# FFB_Arduino_Yoke_1_3_Micro.net
KiCad netlist of a schematic drawn in EasyEDA
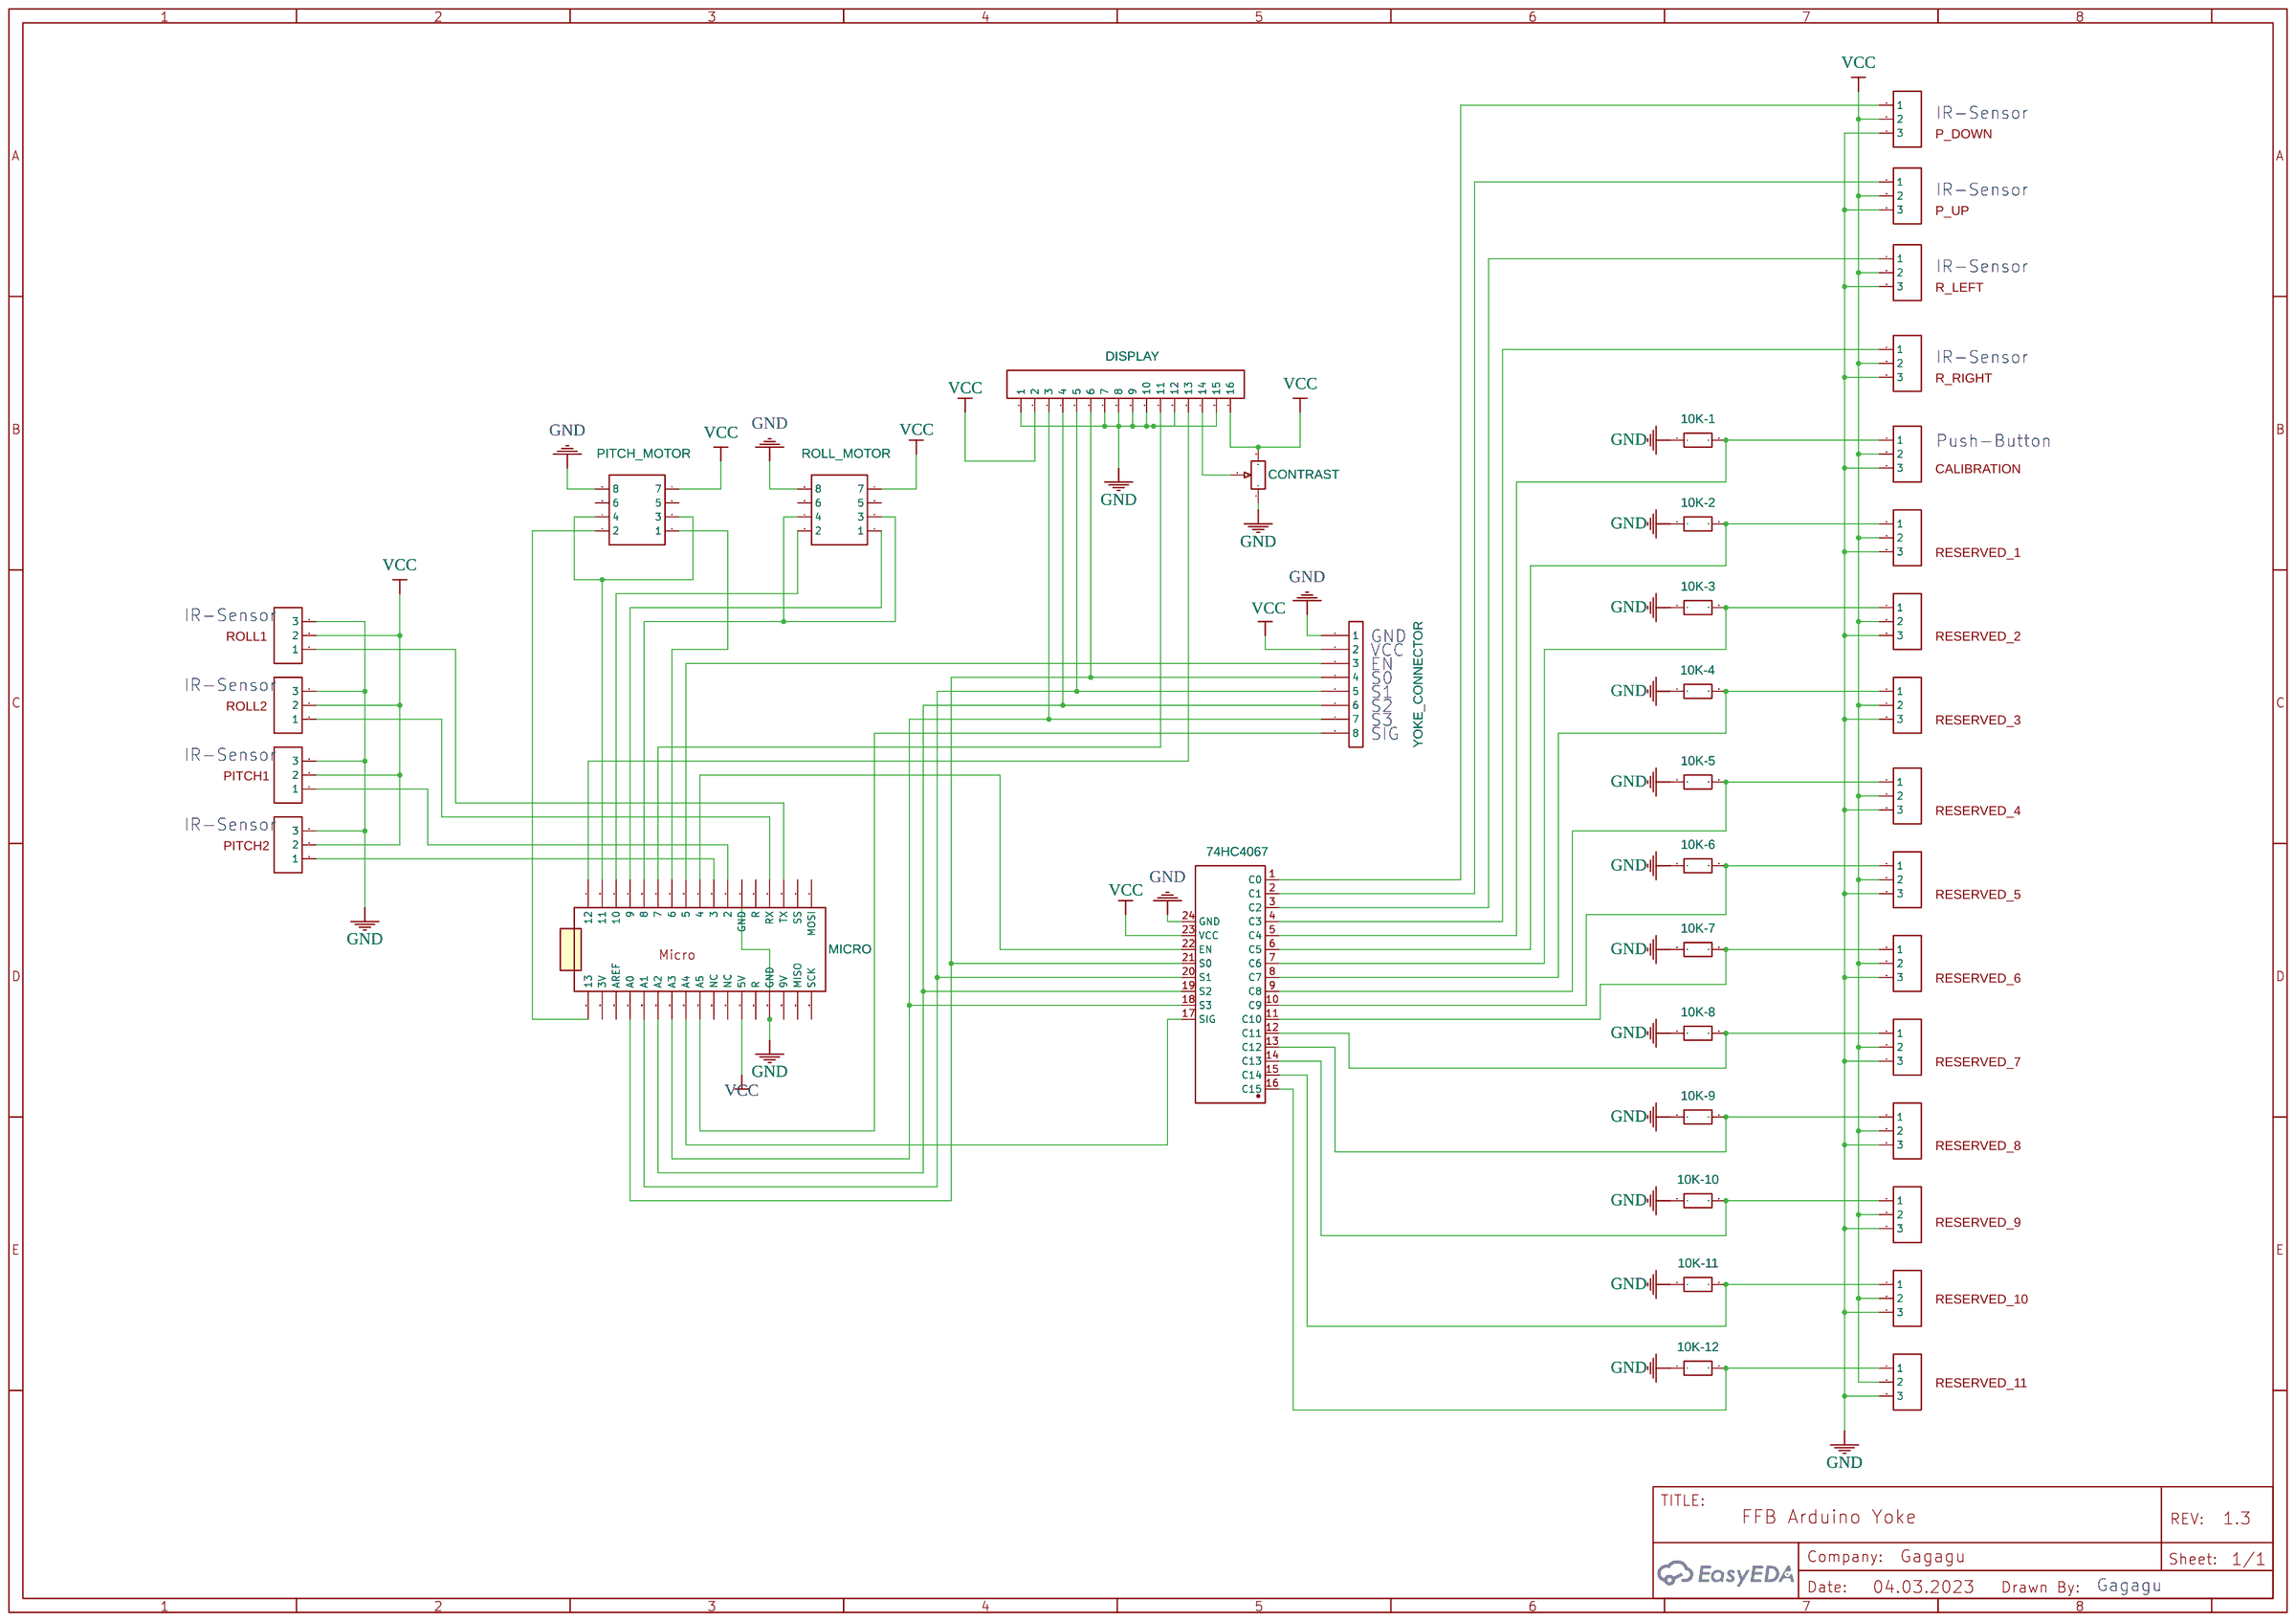
[diagram p0: schematic sheet]

(export (version "E")
  (design (tool "Eeschema 10.0.6"))
  (components
    (comp (ref "10K-1") (value "10k") (libsource (lib "") (part "R_AXIAL-0.3_EU")))
    (comp (ref "10K-2") (value "10k") (libsource (lib "") (part "R_AXIAL-0.3_EU")))
    (comp (ref "10K-3") (value "10k") (libsource (lib "") (part "R_AXIAL-0.3_EU")))
    (comp (ref "10K-4") (value "10k") (libsource (lib "") (part "R_AXIAL-0.3_EU")))
    (comp (ref "10K-5") (value "10k") (libsource (lib "") (part "R_AXIAL-0.3_EU")))
    (comp (ref "10K-6") (value "10k") (libsource (lib "") (part "R_AXIAL-0.3_EU")))
    (comp (ref "10K-7") (value "10k") (libsource (lib "") (part "R_AXIAL-0.3_EU")))
    (comp (ref "10K-8") (value "10k") (libsource (lib "") (part "R_AXIAL-0.3_EU")))
    (comp (ref "10K-9") (value "10k") (libsource (lib "") (part "R_AXIAL-0.3_EU")))
    (comp (ref "10K-10") (value "10k") (libsource (lib "") (part "R_AXIAL-0.3_EU")))
    (comp (ref "10K-11") (value "10k") (libsource (lib "") (part "R_AXIAL-0.3_EU")))
    (comp (ref "10K-12") (value "10k") (libsource (lib "") (part "R_AXIAL-0.3_EU")))
    (comp (ref "74HC4067")
      (value "MUX CD74HC4067")
      (fields (field (name "BOM_Supplier Part") "420243"))
      (libsource (lib "") (part "16-Kanal Analog/Digital Multiplexer MUX CD74HC4067"))
    )
    (comp (ref "CALIBR.")
      (value "Multiturn POT 10K")
      (fields (field (name "BOM_Supplier Part") "C146690"))
      (libsource (lib "") (part "HDR-F-2.54_1x3_9"))
    )
    (comp (ref "CONTRAST") (value "R_3386P_EU") (libsource (lib "") (part "R_3386P_EU")))
    (comp (ref "DISPLAY") (value "HDR-M-2.54_1x16") (libsource (lib "") (part "HDR-M-2.54_1x16")))
    (comp (ref "MICRO") (value "ARDUINOMICRO") (libsource (lib "") (part "ARDUINOMICRO")))
    (comp (ref "PITCH1")
      (value "Multiturn POT 10K")
      (fields (field (name "BOM_Supplier Part") "C146690"))
      (libsource (lib "") (part "HDR-F-2.54_1x3"))
    )
    (comp (ref "PITCH2")
      (value "Multiturn POT 10K")
      (fields (field (name "BOM_Supplier Part") "C146690"))
      (libsource (lib "") (part "HDR-F-2.54_1x3_17"))
    )
    (comp (ref "PITCH_MOTOR")
      (value "HDR-F-2.54_2x4")
      (fields (field (name "BOM_Supplier Part") "C239344"))
      (libsource (lib "") (part "HDR-F-2.54_2x4"))
    )
    (comp (ref "P_DOWN")
      (value "Multiturn POT 10K")
      (fields (field (name "BOM_Supplier Part") "C146690"))
      (libsource (lib "") (part "HDR-F-2.54_1x3_1"))
    )
    (comp (ref "P_UP")
      (value "Multiturn POT 10K")
      (fields (field (name "BOM_Supplier Part") "C146690"))
      (libsource (lib "") (part "HDR-F-2.54_1x3_18"))
    )
    (comp (ref "RES_1")
      (value "Multiturn POT 10K")
      (fields (field (name "BOM_Supplier Part") "C146690"))
      (libsource (lib "") (part "HDR-F-2.54_1x3_6"))
    )
    (comp (ref "RES_2")
      (value "Multiturn POT 10K")
      (fields (field (name "BOM_Supplier Part") "C146690"))
      (libsource (lib "") (part "HDR-F-2.54_1x3_11"))
    )
    (comp (ref "RES_3")
      (value "Multiturn POT 10K")
      (fields (field (name "BOM_Supplier Part") "C146690"))
      (libsource (lib "") (part "HDR-F-2.54_1x3_7"))
    )
    (comp (ref "RES_4")
      (value "Multiturn POT 10K")
      (fields (field (name "BOM_Supplier Part") "C146690"))
      (libsource (lib "") (part "HDR-F-2.54_1x3_19"))
    )
    (comp (ref "RES_5")
      (value "Multiturn POT 10K")
      (fields (field (name "BOM_Supplier Part") "C146690"))
      (libsource (lib "") (part "HDR-F-2.54_1x3_8"))
    )
    (comp (ref "RES_6")
      (value "Multiturn POT 10K")
      (fields (field (name "BOM_Supplier Part") "C146690"))
      (libsource (lib "") (part "HDR-F-2.54_1x3_16"))
    )
    (comp (ref "RES_7")
      (value "Multiturn POT 10K")
      (fields (field (name "BOM_Supplier Part") "C146690"))
      (libsource (lib "") (part "HDR-F-2.54_1x3_3"))
    )
    (comp (ref "RES_8")
      (value "Multiturn POT 10K")
      (fields (field (name "BOM_Supplier Part") "C146690"))
      (libsource (lib "") (part "HDR-F-2.54_1x3_10"))
    )
    (comp (ref "RES_9")
      (value "Multiturn POT 10K")
      (fields (field (name "BOM_Supplier Part") "C146690"))
      (libsource (lib "") (part "HDR-F-2.54_1x3_13"))
    )
    (comp (ref "RES_10")
      (value "Multiturn POT 10K")
      (fields (field (name "BOM_Supplier Part") "C146690"))
      (libsource (lib "") (part "HDR-F-2.54_1x3_14"))
    )
    (comp (ref "RES_11")
      (value "Multiturn POT 10K")
      (fields (field (name "BOM_Supplier Part") "C146690"))
      (libsource (lib "") (part "HDR-F-2.54_1x3_2"))
    )
    (comp (ref "ROLL1")
      (value "Multiturn POT 10K")
      (fields (field (name "BOM_Supplier Part") "C146690"))
      (libsource (lib "") (part "HDR-F-2.54_1x3_4"))
    )
    (comp (ref "ROLL2")
      (value "Multiturn POT 10K")
      (fields (field (name "BOM_Supplier Part") "C146690"))
      (libsource (lib "") (part "HDR-F-2.54_1x3_12"))
    )
    (comp (ref "ROLL_MOTOR")
      (value "HDR-F-2.54_2x4")
      (fields (field (name "BOM_Supplier Part") "C239344"))
      (libsource (lib "") (part "HDR-F-2.54_2x4_1"))
    )
    (comp (ref "R_LEFT")
      (value "Multiturn POT 10K")
      (fields (field (name "BOM_Supplier Part") "C146690"))
      (libsource (lib "") (part "HDR-F-2.54_1x3_15"))
    )
    (comp (ref "R_RIGHT")
      (value "Multiturn POT 10K")
      (fields (field (name "BOM_Supplier Part") "C146690"))
      (libsource (lib "") (part "HDR-F-2.54_1x3_5"))
    )
    (comp (ref "YOKE_CONNECTOR")
      (value "Yoke Connector")
      (fields (field (name "BOM_Manufacturer Part") "Conector_dupont"))
      (libsource (lib "") (part "DUPONT_1X8"))
    )
  )
  (nets
    (net (code "1") (name "GND") (class "Default")
      (node (ref "10K-1") (pin "1") (pinfunction "1_1") (pintype "unspecified"))
      (node (ref "10K-10") (pin "1") (pinfunction "1_1") (pintype "unspecified"))
      (node (ref "10K-11") (pin "1") (pinfunction "1_1") (pintype "unspecified"))
      (node (ref "10K-12") (pin "1") (pinfunction "1_1") (pintype "unspecified"))
      (node (ref "10K-2") (pin "1") (pinfunction "1_1") (pintype "unspecified"))
      (node (ref "10K-3") (pin "1") (pinfunction "1_1") (pintype "unspecified"))
      (node (ref "10K-4") (pin "1") (pinfunction "1_1") (pintype "unspecified"))
      (node (ref "10K-5") (pin "1") (pinfunction "1_1") (pintype "unspecified"))
      (node (ref "10K-6") (pin "1") (pinfunction "1_1") (pintype "unspecified"))
      (node (ref "10K-7") (pin "1") (pinfunction "1_1") (pintype "unspecified"))
      (node (ref "10K-8") (pin "1") (pinfunction "1_1") (pintype "unspecified"))
      (node (ref "10K-9") (pin "1") (pinfunction "1_1") (pintype "unspecified"))
      (node (ref "74HC4067") (pin "24") (pinfunction "GND_24") (pintype "unspecified"))
      (node (ref "CALIBR.") (pin "3") (pinfunction "3_3") (pintype "unspecified"))
      (node (ref "CONTRAST") (pin "1") (pinfunction "1_1") (pintype "input"))
      (node (ref "DISPLAY") (pin "1") (pinfunction "1_1") (pintype "unspecified"))
      (node (ref "DISPLAY") (pin "10") (pinfunction "10_10") (pintype "unspecified"))
      (node (ref "DISPLAY") (pin "12") (pinfunction "12_12") (pintype "unspecified"))
      (node (ref "DISPLAY") (pin "15") (pinfunction "15_15") (pintype "unspecified"))
      (node (ref "DISPLAY") (pin "7") (pinfunction "7_7") (pintype "unspecified"))
      (node (ref "DISPLAY") (pin "8") (pinfunction "8_8") (pintype "unspecified"))
      (node (ref "DISPLAY") (pin "9") (pinfunction "9_9") (pintype "unspecified"))
      (node (ref "MICRO") (pin "P$12") (pinfunction "GND_P$12") (pintype "unspecified"))
      (node (ref "MICRO") (pin "P$21") (pinfunction "GND_P$21") (pintype "unspecified"))
      (node (ref "PITCH1") (pin "3") (pinfunction "3_3") (pintype "unspecified"))
      (node (ref "PITCH2") (pin "3") (pinfunction "3_3") (pintype "unspecified"))
      (node (ref "PITCH_MOTOR") (pin "8") (pinfunction "8_8") (pintype "unspecified"))
      (node (ref "P_DOWN") (pin "3") (pinfunction "3_3") (pintype "unspecified"))
      (node (ref "P_UP") (pin "3") (pinfunction "3_3") (pintype "unspecified"))
      (node (ref "RES_1") (pin "3") (pinfunction "3_3") (pintype "unspecified"))
      (node (ref "RES_10") (pin "3") (pinfunction "3_3") (pintype "unspecified"))
      (node (ref "RES_11") (pin "3") (pinfunction "3_3") (pintype "unspecified"))
      (node (ref "RES_2") (pin "3") (pinfunction "3_3") (pintype "unspecified"))
      (node (ref "RES_3") (pin "3") (pinfunction "3_3") (pintype "unspecified"))
      (node (ref "RES_4") (pin "3") (pinfunction "3_3") (pintype "unspecified"))
      (node (ref "RES_5") (pin "3") (pinfunction "3_3") (pintype "unspecified"))
      (node (ref "RES_6") (pin "3") (pinfunction "3_3") (pintype "unspecified"))
      (node (ref "RES_7") (pin "3") (pinfunction "3_3") (pintype "unspecified"))
      (node (ref "RES_8") (pin "3") (pinfunction "3_3") (pintype "unspecified"))
      (node (ref "RES_9") (pin "3") (pinfunction "3_3") (pintype "unspecified"))
      (node (ref "ROLL1") (pin "3") (pinfunction "3_3") (pintype "unspecified"))
      (node (ref "ROLL2") (pin "3") (pinfunction "3_3") (pintype "unspecified"))
      (node (ref "ROLL_MOTOR") (pin "8") (pinfunction "8_8") (pintype "unspecified"))
      (node (ref "R_LEFT") (pin "3") (pinfunction "3_3") (pintype "unspecified"))
      (node (ref "R_RIGHT") (pin "3") (pinfunction "3_3") (pintype "unspecified"))
      (node (ref "YOKE_CONNECTOR") (pin "1") (pinfunction "1_1") (pintype "unspecified"))
    )
    (net (code "2") (name "Net-(74HC4067-C0)") (class "Default")
      (node (ref "74HC4067") (pin "1") (pinfunction "C0_1") (pintype "unspecified"))
      (node (ref "P_DOWN") (pin "1") (pinfunction "1_1") (pintype "unspecified"))
    )
    (net (code "3") (name "Net-(74HC4067-C1)") (class "Default")
      (node (ref "74HC4067") (pin "2") (pinfunction "C1_2") (pintype "unspecified"))
      (node (ref "P_UP") (pin "1") (pinfunction "1_1") (pintype "unspecified"))
    )
    (net (code "4") (name "Net-(74HC4067-C2)") (class "Default")
      (node (ref "74HC4067") (pin "3") (pinfunction "C2_3") (pintype "unspecified"))
      (node (ref "R_LEFT") (pin "1") (pinfunction "1_1") (pintype "unspecified"))
    )
    (net (code "5") (name "Net-(74HC4067-C3)") (class "Default")
      (node (ref "74HC4067") (pin "4") (pinfunction "C3_4") (pintype "unspecified"))
      (node (ref "R_RIGHT") (pin "1") (pinfunction "1_1") (pintype "unspecified"))
    )
    (net (code "6") (name "Net-(74HC4067-C4)") (class "Default")
      (node (ref "10K-1") (pin "2") (pinfunction "2_2") (pintype "unspecified"))
      (node (ref "74HC4067") (pin "5") (pinfunction "C4_5") (pintype "unspecified"))
      (node (ref "CALIBR.") (pin "1") (pinfunction "1_1") (pintype "unspecified"))
    )
    (net (code "7") (name "Net-(74HC4067-C5)") (class "Default")
      (node (ref "10K-2") (pin "2") (pinfunction "2_2") (pintype "unspecified"))
      (node (ref "74HC4067") (pin "6") (pinfunction "C5_6") (pintype "unspecified"))
      (node (ref "RES_1") (pin "1") (pinfunction "1_1") (pintype "unspecified"))
    )
    (net (code "8") (name "Net-(74HC4067-C6)") (class "Default")
      (node (ref "10K-3") (pin "2") (pinfunction "2_2") (pintype "unspecified"))
      (node (ref "74HC4067") (pin "7") (pinfunction "C6_7") (pintype "unspecified"))
      (node (ref "RES_2") (pin "1") (pinfunction "1_1") (pintype "unspecified"))
    )
    (net (code "9") (name "Net-(74HC4067-C7)") (class "Default")
      (node (ref "10K-4") (pin "2") (pinfunction "2_2") (pintype "unspecified"))
      (node (ref "74HC4067") (pin "8") (pinfunction "C7_8") (pintype "unspecified"))
      (node (ref "RES_3") (pin "1") (pinfunction "1_1") (pintype "unspecified"))
    )
    (net (code "10") (name "Net-(74HC4067-C8)") (class "Default")
      (node (ref "10K-5") (pin "2") (pinfunction "2_2") (pintype "unspecified"))
      (node (ref "74HC4067") (pin "9") (pinfunction "C8_9") (pintype "unspecified"))
      (node (ref "RES_4") (pin "1") (pinfunction "1_1") (pintype "unspecified"))
    )
    (net (code "11") (name "Net-(74HC4067-C9)") (class "Default")
      (node (ref "10K-6") (pin "2") (pinfunction "2_2") (pintype "unspecified"))
      (node (ref "74HC4067") (pin "10") (pinfunction "C9_10") (pintype "unspecified"))
      (node (ref "RES_5") (pin "1") (pinfunction "1_1") (pintype "unspecified"))
    )
    (net (code "12") (name "Net-(74HC4067-C10)") (class "Default")
      (node (ref "10K-7") (pin "2") (pinfunction "2_2") (pintype "unspecified"))
      (node (ref "74HC4067") (pin "11") (pinfunction "C10_11") (pintype "unspecified"))
      (node (ref "RES_6") (pin "1") (pinfunction "1_1") (pintype "unspecified"))
    )
    (net (code "13") (name "Net-(74HC4067-C11)") (class "Default")
      (node (ref "10K-8") (pin "2") (pinfunction "2_2") (pintype "unspecified"))
      (node (ref "74HC4067") (pin "12") (pinfunction "C11_12") (pintype "unspecified"))
      (node (ref "RES_7") (pin "1") (pinfunction "1_1") (pintype "unspecified"))
    )
    (net (code "14") (name "Net-(74HC4067-C12)") (class "Default")
      (node (ref "10K-9") (pin "2") (pinfunction "2_2") (pintype "unspecified"))
      (node (ref "74HC4067") (pin "13") (pinfunction "C12_13") (pintype "unspecified"))
      (node (ref "RES_8") (pin "1") (pinfunction "1_1") (pintype "unspecified"))
    )
    (net (code "15") (name "Net-(74HC4067-C13)") (class "Default")
      (node (ref "10K-10") (pin "2") (pinfunction "2_2") (pintype "unspecified"))
      (node (ref "74HC4067") (pin "14") (pinfunction "C13_14") (pintype "unspecified"))
      (node (ref "RES_9") (pin "1") (pinfunction "1_1") (pintype "unspecified"))
    )
    (net (code "16") (name "Net-(74HC4067-C14)") (class "Default")
      (node (ref "10K-11") (pin "2") (pinfunction "2_2") (pintype "unspecified"))
      (node (ref "74HC4067") (pin "15") (pinfunction "C14_15") (pintype "unspecified"))
      (node (ref "RES_10") (pin "1") (pinfunction "1_1") (pintype "unspecified"))
    )
    (net (code "17") (name "Net-(74HC4067-C15)") (class "Default")
      (node (ref "10K-12") (pin "2") (pinfunction "2_2") (pintype "unspecified"))
      (node (ref "74HC4067") (pin "16") (pinfunction "C15_16") (pintype "unspecified"))
      (node (ref "RES_11") (pin "1") (pinfunction "1_1") (pintype "unspecified"))
    )
    (net (code "18") (name "Net-(74HC4067-EN)") (class "Default")
      (node (ref "74HC4067") (pin "22") (pinfunction "EN_22") (pintype "unspecified"))
      (node (ref "MICRO") (pin "P$9") (pinfunction "4_P$9") (pintype "unspecified"))
    )
    (net (code "19") (name "Net-(74HC4067-S0)") (class "Default")
      (node (ref "74HC4067") (pin "21") (pinfunction "S0_21") (pintype "unspecified"))
      (node (ref "DISPLAY") (pin "6") (pinfunction "6_6") (pintype "unspecified"))
      (node (ref "MICRO") (pin "P$31") (pinfunction "A0_P$31") (pintype "unspecified"))
      (node (ref "YOKE_CONNECTOR") (pin "4") (pinfunction "4_4") (pintype "unspecified"))
    )
    (net (code "20") (name "Net-(74HC4067-S1)") (class "Default")
      (node (ref "74HC4067") (pin "20") (pinfunction "S1_20") (pintype "unspecified"))
      (node (ref "DISPLAY") (pin "5") (pinfunction "5_5") (pintype "unspecified"))
      (node (ref "MICRO") (pin "P$30") (pinfunction "A1_P$30") (pintype "unspecified"))
      (node (ref "YOKE_CONNECTOR") (pin "5") (pinfunction "5_5") (pintype "unspecified"))
    )
    (net (code "21") (name "Net-(74HC4067-S2)") (class "Default")
      (node (ref "74HC4067") (pin "19") (pinfunction "S2_19") (pintype "unspecified"))
      (node (ref "DISPLAY") (pin "4") (pinfunction "4_4") (pintype "unspecified"))
      (node (ref "MICRO") (pin "P$29") (pinfunction "A2_P$29") (pintype "unspecified"))
      (node (ref "YOKE_CONNECTOR") (pin "6") (pinfunction "6_6") (pintype "unspecified"))
    )
    (net (code "22") (name "Net-(74HC4067-S3)") (class "Default")
      (node (ref "74HC4067") (pin "18") (pinfunction "S3_18") (pintype "unspecified"))
      (node (ref "DISPLAY") (pin "3") (pinfunction "3_3") (pintype "unspecified"))
      (node (ref "MICRO") (pin "P$28") (pinfunction "A3_P$28") (pintype "unspecified"))
      (node (ref "YOKE_CONNECTOR") (pin "7") (pinfunction "7_7") (pintype "unspecified"))
    )
    (net (code "23") (name "Net-(74HC4067-SIG)") (class "Default")
      (node (ref "74HC4067") (pin "17") (pinfunction "SIG_17") (pintype "unspecified"))
      (node (ref "MICRO") (pin "P$27") (pinfunction "A4_P$27") (pintype "unspecified"))
    )
    (net (code "24") (name "Net-(CONTRAST-Pad2)") (class "Default")
      (node (ref "CONTRAST") (pin "2") (pinfunction "2_2") (pintype "input"))
      (node (ref "DISPLAY") (pin "14") (pinfunction "14_14") (pintype "unspecified"))
    )
    (net (code "25") (name "Net-(MICRO-2)") (class "Default")
      (node (ref "MICRO") (pin "P$11") (pinfunction "2_P$11") (pintype "unspecified"))
      (node (ref "PITCH1") (pin "1") (pinfunction "1_1") (pintype "unspecified"))
    )
    (net (code "26") (name "Net-(MICRO-3)") (class "Default")
      (node (ref "MICRO") (pin "P$10") (pinfunction "3_P$10") (pintype "unspecified"))
      (node (ref "PITCH2") (pin "1") (pinfunction "1_1") (pintype "unspecified"))
    )
    (net (code "27") (name "Net-(MICRO-5)") (class "Default")
      (node (ref "MICRO") (pin "P$8") (pinfunction "5_P$8") (pintype "unspecified"))
      (node (ref "YOKE_CONNECTOR") (pin "3") (pinfunction "3_3") (pintype "unspecified"))
    )
    (net (code "28") (name "Net-(MICRO-6)") (class "Default")
      (node (ref "MICRO") (pin "P$7") (pinfunction "6_P$7") (pintype "unspecified"))
      (node (ref "PITCH_MOTOR") (pin "1") (pinfunction "1_1") (pintype "unspecified"))
    )
    (net (code "29") (name "Net-(MICRO-7)") (class "Default")
      (node (ref "DISPLAY") (pin "11") (pinfunction "11_11") (pintype "unspecified"))
      (node (ref "MICRO") (pin "P$6") (pinfunction "7_P$6") (pintype "unspecified"))
    )
    (net (code "30") (name "Net-(MICRO-8)") (class "Default")
      (node (ref "MICRO") (pin "P$5") (pinfunction "8_P$5") (pintype "unspecified"))
      (node (ref "ROLL_MOTOR") (pin "3") (pinfunction "3_3") (pintype "unspecified"))
      (node (ref "ROLL_MOTOR") (pin "4") (pinfunction "4_4") (pintype "unspecified"))
    )
    (net (code "31") (name "Net-(MICRO-9)") (class "Default")
      (node (ref "MICRO") (pin "P$4") (pinfunction "9_P$4") (pintype "unspecified"))
      (node (ref "ROLL_MOTOR") (pin "1") (pinfunction "1_1") (pintype "unspecified"))
    )
    (net (code "32") (name "Net-(MICRO-10)") (class "Default")
      (node (ref "MICRO") (pin "P$3") (pinfunction "10_P$3") (pintype "unspecified"))
      (node (ref "ROLL_MOTOR") (pin "2") (pinfunction "2_2") (pintype "unspecified"))
    )
    (net (code "33") (name "Net-(MICRO-11)") (class "Default")
      (node (ref "MICRO") (pin "P$2") (pinfunction "11_P$2") (pintype "unspecified"))
      (node (ref "PITCH_MOTOR") (pin "3") (pinfunction "3_3") (pintype "unspecified"))
      (node (ref "PITCH_MOTOR") (pin "4") (pinfunction "4_4") (pintype "unspecified"))
    )
    (net (code "34") (name "Net-(MICRO-12)") (class "Default")
      (node (ref "DISPLAY") (pin "13") (pinfunction "13_13") (pintype "unspecified"))
      (node (ref "MICRO") (pin "P$1") (pinfunction "12_P$1") (pintype "unspecified"))
    )
    (net (code "35") (name "Net-(MICRO-13)") (class "Default")
      (node (ref "MICRO") (pin "P$34") (pinfunction "13_P$34") (pintype "unspecified"))
      (node (ref "PITCH_MOTOR") (pin "2") (pinfunction "2_2") (pintype "unspecified"))
    )
    (net (code "36") (name "Net-(MICRO-A5)") (class "Default")
      (node (ref "MICRO") (pin "P$26") (pinfunction "A5_P$26") (pintype "unspecified"))
      (node (ref "YOKE_CONNECTOR") (pin "8") (pinfunction "8_8") (pintype "unspecified"))
    )
    (net (code "37") (name "Net-(MICRO-RX)") (class "Default")
      (node (ref "MICRO") (pin "P$14") (pinfunction "RX_P$14") (pintype "unspecified"))
      (node (ref "ROLL2") (pin "1") (pinfunction "1_1") (pintype "unspecified"))
    )
    (net (code "38") (name "Net-(MICRO-TX)") (class "Default")
      (node (ref "MICRO") (pin "P$15") (pinfunction "TX_P$15") (pintype "unspecified"))
      (node (ref "ROLL1") (pin "1") (pinfunction "1_1") (pintype "unspecified"))
    )
    (net (code "39") (name "VCC") (class "Default")
      (node (ref "74HC4067") (pin "23") (pinfunction "VCC_23") (pintype "unspecified"))
      (node (ref "CALIBR.") (pin "2") (pinfunction "2_2") (pintype "unspecified"))
      (node (ref "CONTRAST") (pin "3") (pinfunction "3_3") (pintype "input"))
      (node (ref "DISPLAY") (pin "16") (pinfunction "16_16") (pintype "unspecified"))
      (node (ref "DISPLAY") (pin "2") (pinfunction "2_2") (pintype "unspecified"))
      (node (ref "MICRO") (pin "P$23") (pinfunction "5V_P$23") (pintype "unspecified"))
      (node (ref "PITCH1") (pin "2") (pinfunction "2_2") (pintype "unspecified"))
      (node (ref "PITCH2") (pin "2") (pinfunction "2_2") (pintype "unspecified"))
      (node (ref "PITCH_MOTOR") (pin "7") (pinfunction "7_7") (pintype "unspecified"))
      (node (ref "P_DOWN") (pin "2") (pinfunction "2_2") (pintype "unspecified"))
      (node (ref "P_UP") (pin "2") (pinfunction "2_2") (pintype "unspecified"))
      (node (ref "RES_1") (pin "2") (pinfunction "2_2") (pintype "unspecified"))
      (node (ref "RES_10") (pin "2") (pinfunction "2_2") (pintype "unspecified"))
      (node (ref "RES_11") (pin "2") (pinfunction "2_2") (pintype "unspecified"))
      (node (ref "RES_2") (pin "2") (pinfunction "2_2") (pintype "unspecified"))
      (node (ref "RES_3") (pin "2") (pinfunction "2_2") (pintype "unspecified"))
      (node (ref "RES_4") (pin "2") (pinfunction "2_2") (pintype "unspecified"))
      (node (ref "RES_5") (pin "2") (pinfunction "2_2") (pintype "unspecified"))
      (node (ref "RES_6") (pin "2") (pinfunction "2_2") (pintype "unspecified"))
      (node (ref "RES_7") (pin "2") (pinfunction "2_2") (pintype "unspecified"))
      (node (ref "RES_8") (pin "2") (pinfunction "2_2") (pintype "unspecified"))
      (node (ref "RES_9") (pin "2") (pinfunction "2_2") (pintype "unspecified"))
      (node (ref "ROLL1") (pin "2") (pinfunction "2_2") (pintype "unspecified"))
      (node (ref "ROLL2") (pin "2") (pinfunction "2_2") (pintype "unspecified"))
      (node (ref "ROLL_MOTOR") (pin "7") (pinfunction "7_7") (pintype "unspecified"))
      (node (ref "R_LEFT") (pin "2") (pinfunction "2_2") (pintype "unspecified"))
      (node (ref "R_RIGHT") (pin "2") (pinfunction "2_2") (pintype "unspecified"))
      (node (ref "YOKE_CONNECTOR") (pin "2") (pinfunction "2_2") (pintype "unspecified"))
    )
    (net (code "40") (name "unconnected-(MICRO-3V-PadP$33)") (class "Default")
      (node (ref "MICRO") (pin "P$33") (pinfunction "3V_P$33") (pintype "unspecified"))
    )
    (net (code "41") (name "unconnected-(MICRO-9V-PadP$20)") (class "Default")
      (node (ref "MICRO") (pin "P$20") (pinfunction "9V_P$20") (pintype "unspecified"))
    )
    (net (code "42") (name "unconnected-(MICRO-AREF-PadP$32)") (class "Default")
      (node (ref "MICRO") (pin "P$32") (pinfunction "AREF_P$32") (pintype "unspecified"))
    )
    (net (code "43") (name "unconnected-(MICRO-MISO-PadP$19)") (class "Default")
      (node (ref "MICRO") (pin "P$19") (pinfunction "MISO_P$19") (pintype "unspecified"))
    )
    (net (code "44") (name "unconnected-(MICRO-MOSI-PadP$17)") (class "Default")
      (node (ref "MICRO") (pin "P$17") (pinfunction "MOSI_P$17") (pintype "unspecified"))
    )
    (net (code "45") (name "unconnected-(MICRO-NC-PadP$24)") (class "Default")
      (node (ref "MICRO") (pin "P$24") (pinfunction "NC_P$24") (pintype "unspecified"))
    )
    (net (code "46") (name "unconnected-(MICRO-NC-PadP$25)") (class "Default")
      (node (ref "MICRO") (pin "P$25") (pinfunction "NC_P$25") (pintype "unspecified"))
    )
    (net (code "47") (name "unconnected-(MICRO-R-PadP$13)") (class "Default")
      (node (ref "MICRO") (pin "P$13") (pinfunction "R_P$13") (pintype "unspecified"))
    )
    (net (code "48") (name "unconnected-(MICRO-R-PadP$22)") (class "Default")
      (node (ref "MICRO") (pin "P$22") (pinfunction "R_P$22") (pintype "unspecified"))
    )
    (net (code "49") (name "unconnected-(MICRO-SCK-PadP$18)") (class "Default")
      (node (ref "MICRO") (pin "P$18") (pinfunction "SCK_P$18") (pintype "unspecified"))
    )
    (net (code "50") (name "unconnected-(MICRO-SS-PadP$16)") (class "Default")
      (node (ref "MICRO") (pin "P$16") (pinfunction "SS_P$16") (pintype "unspecified"))
    )
    (net (code "51") (name "unconnected-(PITCH_MOTOR-Pad5)") (class "Default")
      (node (ref "PITCH_MOTOR") (pin "5") (pinfunction "5_5") (pintype "unspecified"))
    )
    (net (code "52") (name "unconnected-(PITCH_MOTOR-Pad6)") (class "Default")
      (node (ref "PITCH_MOTOR") (pin "6") (pinfunction "6_6") (pintype "unspecified"))
    )
    (net (code "53") (name "unconnected-(ROLL_MOTOR-Pad5)") (class "Default")
      (node (ref "ROLL_MOTOR") (pin "5") (pinfunction "5_5") (pintype "unspecified"))
    )
    (net (code "54") (name "unconnected-(ROLL_MOTOR-Pad6)") (class "Default")
      (node (ref "ROLL_MOTOR") (pin "6") (pinfunction "6_6") (pintype "unspecified"))
    )
  )
)
